# Sample_Tiny861.net
KiCad netlist of a schematic drawn in EAGLE
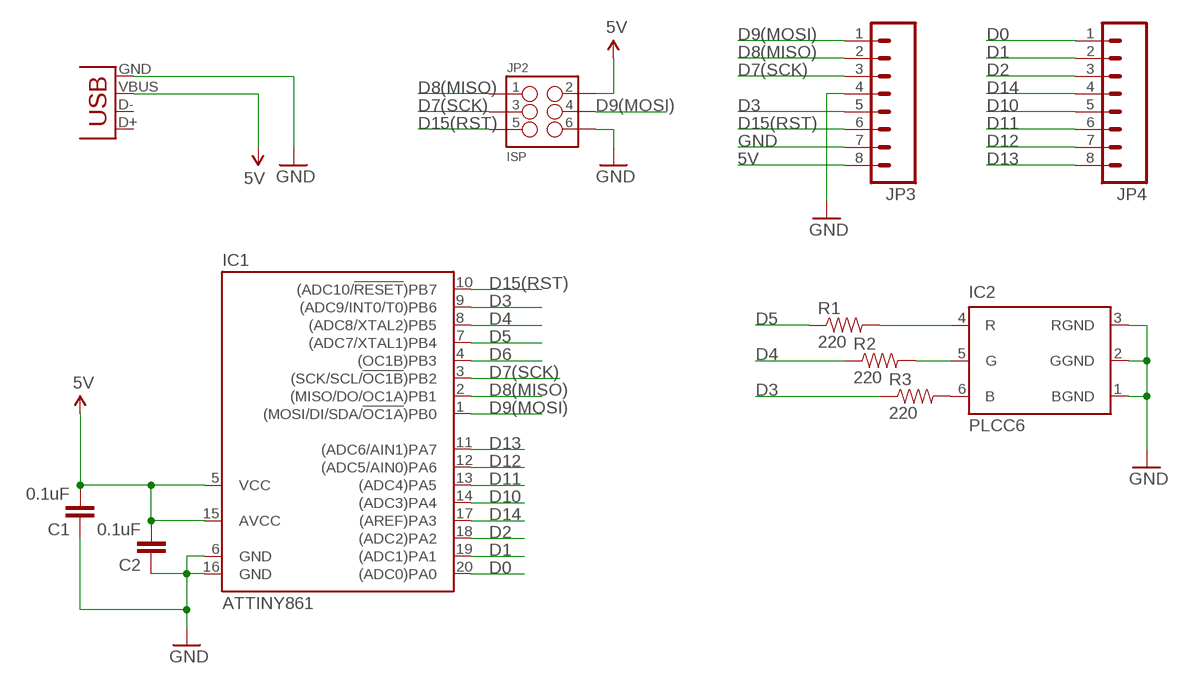
[diagram p0: schematic, sheet 1]

(export (version "E")
  (design (tool "Eeschema 10.0.6"))
  (components
    (comp (ref "C1")
      (value "0.1uF")
      (footprint "eagle-import:0603-CAP")
      (libsource (lib "eagle-import") (part "1.0UF-16V-10%(0603)"))
    )
    (comp (ref "C2")
      (value "0.1uF")
      (footprint "eagle-import:0603-CAP")
      (libsource (lib "eagle-import") (part "1.0UF-16V-10%(0603)"))
    )
    (comp (ref "IC1")
      (value "ATTINY861")
      (footprint "eagle-import:SO20L")
      (fields (field (name "MPN") "ATTINY26L-8SU"))
      (libsource (lib "eagle-import") (part "TINY26SL"))
    )
    (comp (ref "IC2")
      (value "PLCC6")
      (footprint "eagle-import:PLCC6")
      (libsource (lib "eagle-import") (part "PLCC6"))
    )
    (comp (ref "JP1")
      (value "USBSMD")
      (footprint "eagle-import:USB-MINIB")
      (libsource (lib "eagle-import") (part "USBSMD"))
    )
    (comp (ref "JP2")
      (value "ISP")
      (footprint "eagle-import:2X3")
      (libsource (lib "eagle-import") (part "M03X22X3_SILK_SM"))
    )
    (comp (ref "JP3")
      (value "M08")
      (footprint "eagle-import:1X08_PIN1_NO_SILK")
      (libsource (lib "eagle-import") (part "M08"))
    )
    (comp (ref "JP4")
      (value "M08")
      (footprint "eagle-import:1X08_PIN1_NO_SILK")
      (libsource (lib "eagle-import") (part "M08"))
    )
    (comp (ref "R1")
      (value "220")
      (footprint "eagle-import:0603-RES")
      (libsource (lib "eagle-import") (part "RESISTOR0603"))
    )
    (comp (ref "R2")
      (value "220")
      (footprint "eagle-import:0603-RES")
      (libsource (lib "eagle-import") (part "RESISTOR0603"))
    )
    (comp (ref "R3")
      (value "220")
      (footprint "eagle-import:0603-RES")
      (libsource (lib "eagle-import") (part "RESISTOR0603"))
    )
  )
  (nets
    (net (code "1") (name "/D0") (class "Default")
      (node (ref "IC1") (pin "20") (pinfunction "(ADC0)PA0_20") (pintype "bidirectional"))
      (node (ref "JP4") (pin "1") (pinfunction "1_1") (pintype "passive"))
    )
    (net (code "2") (name "/D1") (class "Default")
      (node (ref "IC1") (pin "19") (pinfunction "(ADC1)PA1_19") (pintype "bidirectional"))
      (node (ref "JP4") (pin "2") (pinfunction "2_2") (pintype "passive"))
    )
    (net (code "3") (name "/D2") (class "Default")
      (node (ref "IC1") (pin "18") (pinfunction "(ADC2)PA2_18") (pintype "bidirectional"))
      (node (ref "JP4") (pin "3") (pinfunction "3_3") (pintype "passive"))
    )
    (net (code "4") (name "/D3") (class "Default")
      (node (ref "IC1") (pin "9") (pinfunction "(ADC9/INT0/T0)PB6_9") (pintype "bidirectional"))
      (node (ref "JP3") (pin "5") (pinfunction "5_5") (pintype "passive"))
      (node (ref "R3") (pin "1") (pinfunction "1_1") (pintype "passive"))
    )
    (net (code "5") (name "/D4") (class "Default")
      (node (ref "IC1") (pin "8") (pinfunction "(ADC8/XTAL2)PB5_8") (pintype "bidirectional"))
      (node (ref "R2") (pin "1") (pinfunction "1_1") (pintype "passive"))
    )
    (net (code "6") (name "/D5") (class "Default")
      (node (ref "IC1") (pin "7") (pinfunction "(ADC7/XTAL1)PB4_7") (pintype "bidirectional"))
      (node (ref "R1") (pin "1") (pinfunction "1_1") (pintype "passive"))
    )
    (net (code "7") (name "/D6") (class "Default")
      (node (ref "IC1") (pin "4") (pinfunction "(OC1B)PB3_4") (pintype "bidirectional"))
    )
    (net (code "8") (name "/D7(SCK)") (class "Default")
      (node (ref "IC1") (pin "3") (pinfunction "(SCK/SCL/~{OC1B})PB2_3") (pintype "bidirectional"))
      (node (ref "JP2") (pin "3") (pinfunction "3_3") (pintype "bidirectional"))
      (node (ref "JP3") (pin "3") (pinfunction "3_3") (pintype "passive"))
    )
    (net (code "9") (name "/D8(MISO)") (class "Default")
      (node (ref "IC1") (pin "2") (pinfunction "(MISO/DO/OC1A)PB1_2") (pintype "bidirectional"))
      (node (ref "JP2") (pin "1") (pinfunction "1_1") (pintype "bidirectional"))
      (node (ref "JP3") (pin "2") (pinfunction "2_2") (pintype "passive"))
    )
    (net (code "10") (name "/D9(MOSI)") (class "Default")
      (node (ref "IC1") (pin "1") (pinfunction "(MOSI/DI/SDA/~{OC1A})PB0_1") (pintype "bidirectional"))
      (node (ref "JP2") (pin "4") (pinfunction "4_4") (pintype "bidirectional"))
      (node (ref "JP3") (pin "1") (pinfunction "1_1") (pintype "passive"))
    )
    (net (code "11") (name "/D10") (class "Default")
      (node (ref "IC1") (pin "14") (pinfunction "(ADC3)PA4_14") (pintype "bidirectional"))
      (node (ref "JP4") (pin "5") (pinfunction "5_5") (pintype "passive"))
    )
    (net (code "12") (name "/D11") (class "Default")
      (node (ref "IC1") (pin "13") (pinfunction "(ADC4)PA5_13") (pintype "bidirectional"))
      (node (ref "JP4") (pin "6") (pinfunction "6_6") (pintype "passive"))
    )
    (net (code "13") (name "/D12") (class "Default")
      (node (ref "IC1") (pin "12") (pinfunction "(ADC5/AIN0)PA6_12") (pintype "bidirectional"))
      (node (ref "JP4") (pin "7") (pinfunction "7_7") (pintype "passive"))
    )
    (net (code "14") (name "/D13") (class "Default")
      (node (ref "IC1") (pin "11") (pinfunction "(ADC6/AIN1)PA7_11") (pintype "bidirectional"))
      (node (ref "JP4") (pin "8") (pinfunction "8_8") (pintype "passive"))
    )
    (net (code "15") (name "/D14") (class "Default")
      (node (ref "IC1") (pin "17") (pinfunction "(AREF)PA3_17") (pintype "bidirectional"))
      (node (ref "JP4") (pin "4") (pinfunction "4_4") (pintype "passive"))
    )
    (net (code "16") (name "/D15(RST)") (class "Default")
      (node (ref "IC1") (pin "10") (pinfunction "(ADC10/~{RESET})PB7_10") (pintype "bidirectional"))
      (node (ref "JP2") (pin "5") (pinfunction "5_5") (pintype "bidirectional"))
      (node (ref "JP3") (pin "6") (pinfunction "6_6") (pintype "passive"))
    )
    (net (code "17") (name "5V") (class "Default")
      (node (ref "C1") (pin "2") (pinfunction "2_2") (pintype "passive"))
      (node (ref "C2") (pin "2") (pinfunction "2_2") (pintype "passive"))
      (node (ref "IC1") (pin "15") (pinfunction "AVCC_15") (pintype "power_in"))
      (node (ref "IC1") (pin "5") (pinfunction "VCC_5") (pintype "power_in"))
      (node (ref "JP1") (pin "VBUS") (pinfunction "VBUS_VBUS") (pintype "bidirectional"))
      (node (ref "JP2") (pin "2") (pinfunction "2_2") (pintype "bidirectional"))
      (node (ref "JP3") (pin "8") (pinfunction "8_8") (pintype "passive"))
    )
    (net (code "18") (name "GND") (class "Default")
      (node (ref "C1") (pin "1") (pinfunction "1_1") (pintype "passive"))
      (node (ref "C2") (pin "1") (pinfunction "1_1") (pintype "passive"))
      (node (ref "IC1") (pin "16") (pinfunction "GND_16") (pintype "power_in"))
      (node (ref "IC1") (pin "6") (pinfunction "GND_6") (pintype "power_in"))
      (node (ref "IC2") (pin "1") (pinfunction "BGND_1") (pintype "bidirectional"))
      (node (ref "IC2") (pin "2") (pinfunction "GGND_2") (pintype "bidirectional"))
      (node (ref "IC2") (pin "3") (pinfunction "RGND_3") (pintype "bidirectional"))
      (node (ref "JP1") (pin "GND") (pinfunction "GND_GND") (pintype "bidirectional"))
      (node (ref "JP2") (pin "6") (pinfunction "6_6") (pintype "bidirectional"))
      (node (ref "JP3") (pin "4") (pinfunction "4_4") (pintype "passive"))
      (node (ref "JP3") (pin "7") (pinfunction "7_7") (pintype "passive"))
    )
    (net (code "19") (name "Net-(IC2-B)") (class "Default")
      (node (ref "IC2") (pin "6") (pinfunction "B_6") (pintype "bidirectional"))
      (node (ref "R3") (pin "2") (pinfunction "2_2") (pintype "passive"))
    )
    (net (code "20") (name "Net-(IC2-G)") (class "Default")
      (node (ref "IC2") (pin "5") (pinfunction "G_5") (pintype "bidirectional"))
      (node (ref "R2") (pin "2") (pinfunction "2_2") (pintype "passive"))
    )
    (net (code "21") (name "Net-(IC2-R)") (class "Default")
      (node (ref "IC2") (pin "4") (pinfunction "R_4") (pintype "bidirectional"))
      (node (ref "R1") (pin "2") (pinfunction "2_2") (pintype "passive"))
    )
    (net (code "22") (name "unconnected-(JP1-PadD+)") (class "Default")
      (node (ref "JP1") (pin "D+") (pinfunction "D+_D+") (pintype "bidirectional"))
    )
    (net (code "23") (name "unconnected-(JP1-PadD-)") (class "Default")
      (node (ref "JP1") (pin "D-") (pinfunction "D-_D-") (pintype "bidirectional"))
    )
  )
)
